# anemometer-r4.net
KiCad netlist of a schematic drawn in EAGLE
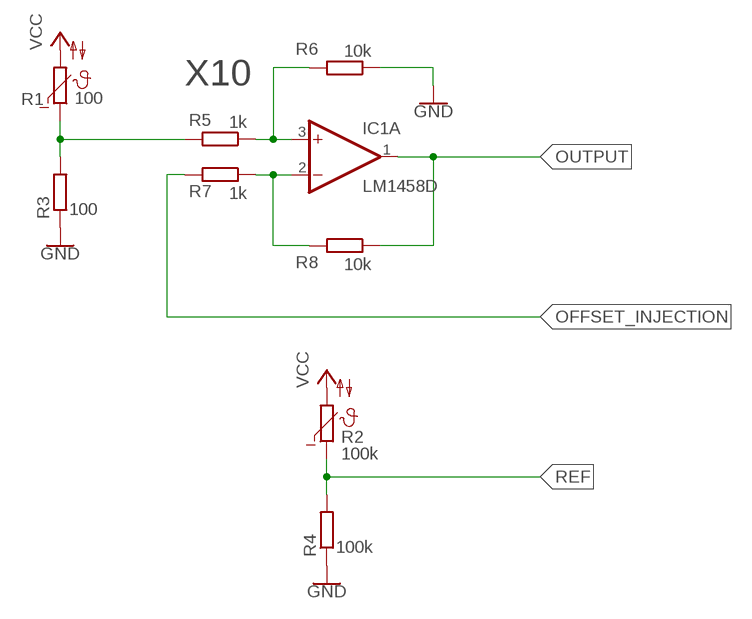
[diagram p0: schematic, sheet 1]

(export (version "E")
  (design (tool "Eeschema 10.0.6"))
  (components
    (comp (ref "IC1")
      (value "LM1458D")
      (footprint "eagle-import:SO08")
      (libsource (lib "eagle-import") (part "1458DLM"))
    )
    (comp (ref "R1")
      (value "100")
      (footprint "eagle-import:N640")
      (libsource (lib "eagle-import") (part "NTC640-9"))
    )
    (comp (ref "R2")
      (value "100k")
      (footprint "eagle-import:N640")
      (libsource (lib "eagle-import") (part "NTC640-9"))
    )
    (comp (ref "R3")
      (value "100")
      (footprint "eagle-import:0414V")
      (libsource (lib "eagle-import") (part "R-EU_0414/5V"))
    )
    (comp (ref "R4")
      (value "100k")
      (footprint "eagle-import:0414V")
      (libsource (lib "eagle-import") (part "R-EU_0414/5V"))
    )
    (comp (ref "R5")
      (value "1k")
      (footprint "eagle-import:0414V")
      (libsource (lib "eagle-import") (part "R-EU_0414/5V"))
    )
    (comp (ref "R6")
      (value "10k")
      (footprint "eagle-import:0414V")
      (libsource (lib "eagle-import") (part "R-EU_0414/5V"))
    )
    (comp (ref "R7")
      (value "1k")
      (footprint "eagle-import:0414V")
      (libsource (lib "eagle-import") (part "R-EU_0414/5V"))
    )
    (comp (ref "R8")
      (value "10k")
      (footprint "eagle-import:0414V")
      (libsource (lib "eagle-import") (part "R-EU_0414/5V"))
    )
  )
  (nets
    (net (code "1") (name "GND") (class "Default")
      (node (ref "R3") (pin "1") (pinfunction "1_1") (pintype "passive"))
      (node (ref "R4") (pin "1") (pinfunction "1_1") (pintype "passive"))
      (node (ref "R6") (pin "1") (pinfunction "1_1") (pintype "passive"))
    )
    (net (code "2") (name "Net-(IC1A-+IN)") (class "Default")
      (node (ref "IC1") (pin "3") (pinfunction "+IN_3") (pintype "input"))
      (node (ref "R5") (pin "1") (pinfunction "1_1") (pintype "passive"))
      (node (ref "R6") (pin "2") (pinfunction "2_2") (pintype "passive"))
    )
    (net (code "3") (name "Net-(IC1A--IN)") (class "Default")
      (node (ref "IC1") (pin "2") (pinfunction "-IN_2") (pintype "input"))
      (node (ref "R7") (pin "1") (pinfunction "1_1") (pintype "passive"))
      (node (ref "R8") (pin "2") (pinfunction "2_2") (pintype "passive"))
    )
    (net (code "4") (name "Net-(R1-Pad1)") (class "Default")
      (node (ref "R1") (pin "1") (pinfunction "1_1") (pintype "passive"))
      (node (ref "R3") (pin "2") (pinfunction "2_2") (pintype "passive"))
      (node (ref "R5") (pin "2") (pinfunction "2_2") (pintype "passive"))
    )
    (net (code "5") (name "OFFSET_INJECTION") (class "Default")
      (node (ref "R7") (pin "2") (pinfunction "2_2") (pintype "passive"))
    )
    (net (code "6") (name "OUTPUT") (class "Default")
      (node (ref "IC1") (pin "1") (pinfunction "OUT_1") (pintype "output"))
      (node (ref "R8") (pin "1") (pinfunction "1_1") (pintype "passive"))
    )
    (net (code "7") (name "REF") (class "Default")
      (node (ref "R2") (pin "1") (pinfunction "1_1") (pintype "passive"))
      (node (ref "R4") (pin "2") (pinfunction "2_2") (pintype "passive"))
    )
    (net (code "8") (name "VCC") (class "Default")
      (node (ref "R1") (pin "2") (pinfunction "2_2") (pintype "passive"))
      (node (ref "R2") (pin "2") (pinfunction "2_2") (pintype "passive"))
    )
  )
)
